# TP_IHM_MAIN.net
KiCad netlist of a schematic drawn in Altium Designer
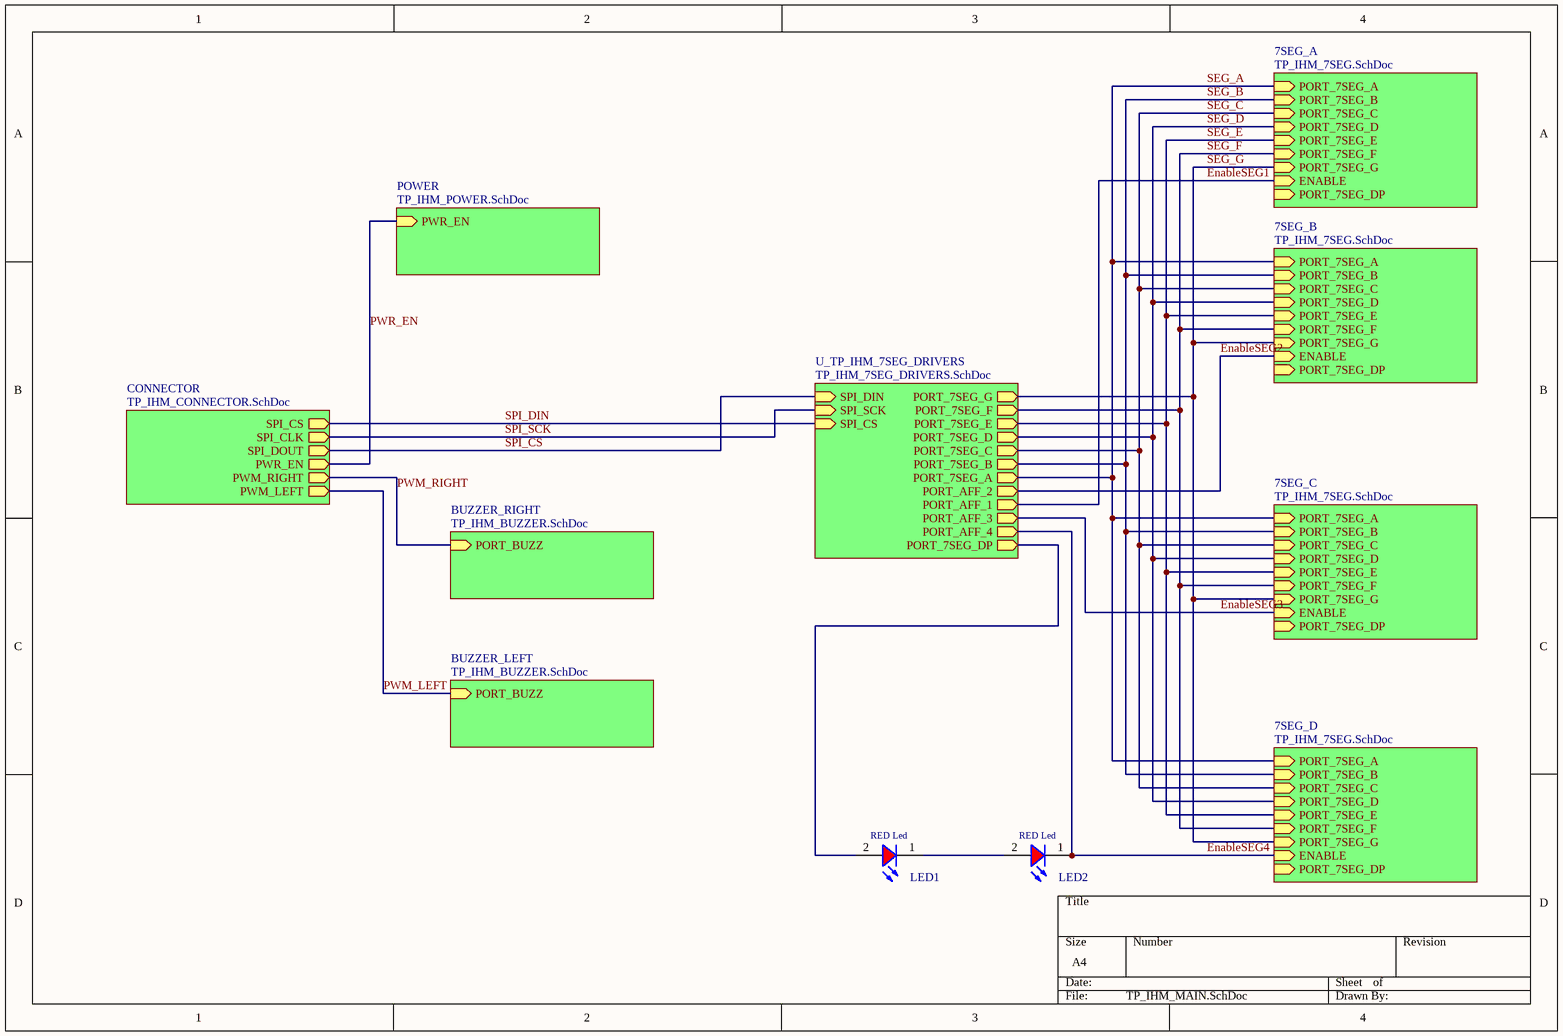
[diagram p0: TP_IHM_MAIN.SchDoc]

(export (version "E")
  (design (tool "Eeschema 10.0.6"))
  (components
    (comp (ref "LED1")
      (value "RED Led")
      (footprint "LED_0603_RED")
      (description "LED RED SMD WE 150060RS750x0")
      (libsource (lib "TpGiven") (part "LED_RED_SMD_WE_150060RS750x0"))
    )
    (comp (ref "LED2")
      (value "RED Led")
      (footprint "LED_0603_RED")
      (description "LED RED SMD WE 150060RS750x0")
      (libsource (lib "TpGiven") (part "LED_RED_SMD_WE_150060RS750x0"))
    )
  )
  (nets
    (net (code "4") (name "/EnableSEG4") (class "Default")
      (node (ref "LED2") (pin "1") (pinfunction "K_1") (pintype "passive"))
    )
    (net (code "6") (name "/PORT_7SEG_DP_1") (class "Default")
      (node (ref "LED1") (pin "2") (pinfunction "A_2") (pintype "passive"))
    )
    (net (code "23") (name "Net-(LED1-K)") (class "Default")
      (node (ref "LED1") (pin "1") (pinfunction "K_1") (pintype "passive"))
      (node (ref "LED2") (pin "2") (pinfunction "A_2") (pintype "passive"))
    )
  )
)
